# communication.net
KiCad netlist of a schematic drawn in Altium Designer
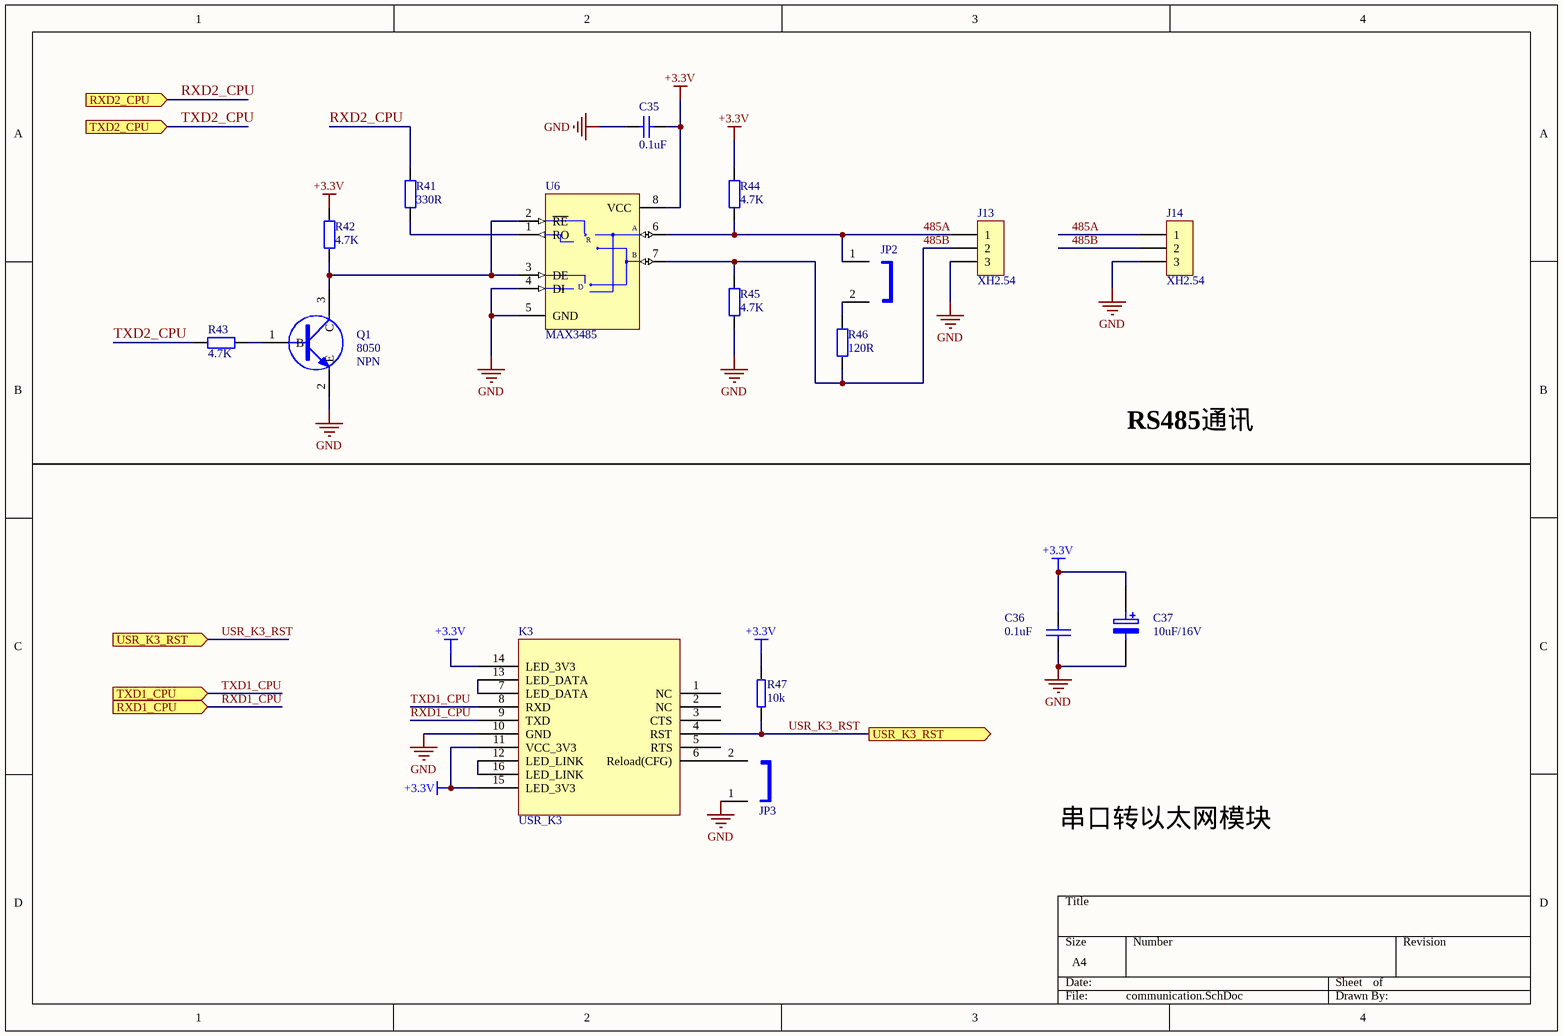
[diagram p0: communication.SchDoc]

(export (version "E")
  (design (tool "Eeschema 10.0.6"))
  (components
    (comp (ref "C35")
      (value "0.1uF")
      (footprint "0805_CAP")
      (description "Capacitor")
      (fields (field (name "PUBLISHER") "Altium Limited"))
      (libsource (lib "Miscellaneous Devices") (part "Cap"))
    )
    (comp (ref "C36")
      (value "0.1uF")
      (footprint "0805_CAP")
      (description "Capacitor")
      (libsource (lib "Mylib") (part "CAP"))
    )
    (comp (ref "C37")
      (value "10uF/16V")
      (footprint "CASE-A_3216")
      (description "Electrolytic Capacitor")
      (libsource (lib "Mylib") (part "ELECTRO2"))
    )
    (comp (ref "J13")
      (value "XH2.54")
      (footprint "XH2,.54-3P")
      (description "Connector")
      (libsource (lib "my") (part "CON3"))
    )
    (comp (ref "J14")
      (value "XH2.54")
      (footprint "XH2,.54-3P")
      (description "Connector")
      (libsource (lib "MyLibrary") (part "CON3"))
    )
    (comp (ref "JP2")
      (value "JUMPER")
      (footprint "SIP2")
      (description "Jumper")
      (libsource (lib "my") (part "JUMPER"))
    )
    (comp (ref "JP3")
      (value "JUMPER")
      (footprint "SIP2")
      (description "Jumper")
      (libsource (lib "Mylib") (part "JUMPER"))
    )
    (comp (ref "K3") (value "USR_K3") (footprint "USR-K3") (libsource (lib "Mylib") (part "USR-K")))
    (comp (ref "Q1") (value "8050") (footprint "SOT-23") (libsource (lib "my") (part "3NPN_SO_1")))
    (comp (ref "R41")
      (value "330R")
      (footprint "0805_RES")
      (description "Resistor")
      (fields (field (name "PUBLISHER") "Altium Limited"))
      (libsource (lib "Miscellaneous Devices") (part "Res2"))
    )
    (comp (ref "R42")
      (value "4.7K")
      (footprint "0805_RES")
      (description "Resistor")
      (fields (field (name "PUBLISHER") "Altium Limited"))
      (libsource (lib "Miscellaneous Devices") (part "Res2"))
    )
    (comp (ref "R43")
      (value "4.7K")
      (footprint "0805_RES")
      (description "Resistor")
      (fields (field (name "PUBLISHER") "Altium Limited"))
      (libsource (lib "") (part "Res2_1"))
    )
    (comp (ref "R44")
      (value "4.7K")
      (footprint "0805_RES")
      (description "Resistor")
      (fields (field (name "PUBLISHER") "Altium Limited"))
      (libsource (lib "Miscellaneous Devices") (part "Res2"))
    )
    (comp (ref "R45")
      (value "4.7K")
      (footprint "0805_RES")
      (description "Resistor")
      (fields (field (name "PUBLISHER") "Altium Limited"))
      (libsource (lib "Miscellaneous Devices") (part "Res2"))
    )
    (comp (ref "R46")
      (value "120R")
      (footprint "0805_RES")
      (description "Resistor")
      (fields (field (name "PUBLISHER") "Altium Limited"))
      (libsource (lib "Miscellaneous Devices") (part "Res2"))
    )
    (comp (ref "R47") (value "10k") (footprint "0805_RES") (libsource (lib "Mylib") (part "RES")))
    (comp (ref "U6") (value "MAX3485") (footprint "SOIC-8_150mil") (libsource (lib "my") (part "MAX485")))
  )
  (nets
    (net (code "1") (name "+3.3V") (class "Default")
      (node (ref "C35") (pin "2") (pinfunction "2_2") (pintype "passive"))
      (node (ref "C36") (pin "1") (pinfunction "1_1") (pintype "passive"))
      (node (ref "C37") (pin "1") (pinfunction "1_1") (pintype "passive"))
      (node (ref "K3") (pin "11") (pinfunction "VCC_3V3_11") (pintype "passive"))
      (node (ref "K3") (pin "14") (pinfunction "LED_3V3_14") (pintype "passive"))
      (node (ref "K3") (pin "15") (pinfunction "LED_3V3_15") (pintype "passive"))
      (node (ref "R42") (pin "2") (pinfunction "2_2") (pintype "passive"))
      (node (ref "R44") (pin "2") (pinfunction "2_2") (pintype "passive"))
      (node (ref "R47") (pin "2") (pinfunction "2_2") (pintype "passive"))
      (node (ref "U6") (pin "8") (pinfunction "VCC_8") (pintype "power_in"))
    )
    (net (code "2") (name "/485A") (class "Default")
      (node (ref "J13") (pin "1") (pinfunction "1_1") (pintype "passive"))
      (node (ref "J14") (pin "1") (pinfunction "1_1") (pintype "passive"))
      (node (ref "JP2") (pin "1") (pinfunction "1_1") (pintype "passive"))
      (node (ref "R44") (pin "1") (pinfunction "1_1") (pintype "passive"))
      (node (ref "U6") (pin "6") (pinfunction "A_6") (pintype "bidirectional"))
    )
    (net (code "3") (name "/485B") (class "Default")
      (node (ref "J13") (pin "2") (pinfunction "2_2") (pintype "passive"))
      (node (ref "J14") (pin "2") (pinfunction "2_2") (pintype "passive"))
      (node (ref "R45") (pin "2") (pinfunction "2_2") (pintype "passive"))
      (node (ref "R46") (pin "1") (pinfunction "1_1") (pintype "passive"))
      (node (ref "U6") (pin "7") (pinfunction "B_7") (pintype "bidirectional"))
    )
    (net (code "4") (name "/RXD1_CPU") (class "Default")
      (node (ref "K3") (pin "9") (pinfunction "TXD_9") (pintype "passive"))
    )
    (net (code "5") (name "/RXD2_CPU") (class "Default")
      (node (ref "R41") (pin "2") (pinfunction "2_2") (pintype "passive"))
    )
    (net (code "6") (name "/TXD1_CPU") (class "Default")
      (node (ref "K3") (pin "8") (pinfunction "RXD_8") (pintype "passive"))
    )
    (net (code "7") (name "/TXD2_CPU") (class "Default")
      (node (ref "R43") (pin "1") (pinfunction "1_1") (pintype "passive"))
    )
    (net (code "8") (name "/USR_K3_RST") (class "Default")
      (node (ref "K3") (pin "4") (pinfunction "RST_4") (pintype "passive"))
      (node (ref "R47") (pin "1") (pinfunction "1_1") (pintype "passive"))
    )
    (net (code "9") (name "GND") (class "Default")
      (node (ref "C35") (pin "1") (pinfunction "1_1") (pintype "passive"))
      (node (ref "C36") (pin "2") (pinfunction "2_2") (pintype "passive"))
      (node (ref "C37") (pin "2") (pinfunction "2_2") (pintype "passive"))
      (node (ref "J13") (pin "3") (pinfunction "3_3") (pintype "passive"))
      (node (ref "J14") (pin "3") (pinfunction "3_3") (pintype "passive"))
      (node (ref "JP3") (pin "1") (pinfunction "1_1") (pintype "passive"))
      (node (ref "K3") (pin "10") (pinfunction "GND_10") (pintype "passive"))
      (node (ref "Q1") (pin "2") (pinfunction "E_2") (pintype "passive"))
      (node (ref "R45") (pin "1") (pinfunction "1_1") (pintype "passive"))
      (node (ref "U6") (pin "4") (pinfunction "DI_4") (pintype "input"))
      (node (ref "U6") (pin "5") (pinfunction "GND_5") (pintype "power_in"))
    )
    (net (code "10") (name "Net-(JP2-Pad2)") (class "Default")
      (node (ref "JP2") (pin "2") (pinfunction "2_2") (pintype "passive"))
      (node (ref "R46") (pin "2") (pinfunction "2_2") (pintype "passive"))
    )
    (net (code "11") (name "Net-(K3-LED_DATA-Pad13)") (class "Default")
      (node (ref "K3") (pin "13") (pinfunction "LED_DATA_13") (pintype "passive"))
      (node (ref "K3") (pin "7") (pinfunction "LED_DATA_7") (pintype "passive"))
    )
    (net (code "12") (name "Net-(K3-LED_LINK-Pad12)") (class "Default")
      (node (ref "K3") (pin "12") (pinfunction "LED_LINK_12") (pintype "passive"))
      (node (ref "K3") (pin "16") (pinfunction "LED_LINK_16") (pintype "passive"))
    )
    (net (code "13") (name "Net-(K3-Reload(CFG))") (class "Default")
      (node (ref "JP3") (pin "2") (pinfunction "2_2") (pintype "passive"))
      (node (ref "K3") (pin "6") (pinfunction "Reload(CFG)_6") (pintype "passive"))
    )
    (net (code "14") (name "Net-(Q1-B)") (class "Default")
      (node (ref "Q1") (pin "1") (pinfunction "B_1") (pintype "passive"))
      (node (ref "R43") (pin "2") (pinfunction "2_2") (pintype "passive"))
    )
    (net (code "15") (name "Net-(Q1-C)") (class "Default")
      (node (ref "Q1") (pin "3") (pinfunction "C_3") (pintype "passive"))
      (node (ref "R42") (pin "1") (pinfunction "1_1") (pintype "passive"))
      (node (ref "U6") (pin "2") (pinfunction "~{RE}_2") (pintype "input"))
      (node (ref "U6") (pin "3") (pinfunction "DE_3") (pintype "input"))
    )
    (net (code "16") (name "Net-(U6-RO)") (class "Default")
      (node (ref "R41") (pin "1") (pinfunction "1_1") (pintype "passive"))
      (node (ref "U6") (pin "1") (pinfunction "RO_1") (pintype "output"))
    )
    (net (code "17") (name "unconnected-(K3-CTS-Pad3)") (class "Default")
      (node (ref "K3") (pin "3") (pinfunction "CTS_3") (pintype "passive"))
    )
    (net (code "18") (name "unconnected-(K3-NC-Pad1)") (class "Default")
      (node (ref "K3") (pin "1") (pinfunction "NC_1") (pintype "passive"))
    )
    (net (code "19") (name "unconnected-(K3-NC-Pad2)") (class "Default")
      (node (ref "K3") (pin "2") (pinfunction "NC_2") (pintype "passive"))
    )
    (net (code "20") (name "unconnected-(K3-RTS-Pad5)") (class "Default")
      (node (ref "K3") (pin "5") (pinfunction "RTS_5") (pintype "passive"))
    )
  )
)
